# AESP_One_01.net
KiCad netlist of a schematic drawn in EAGLE
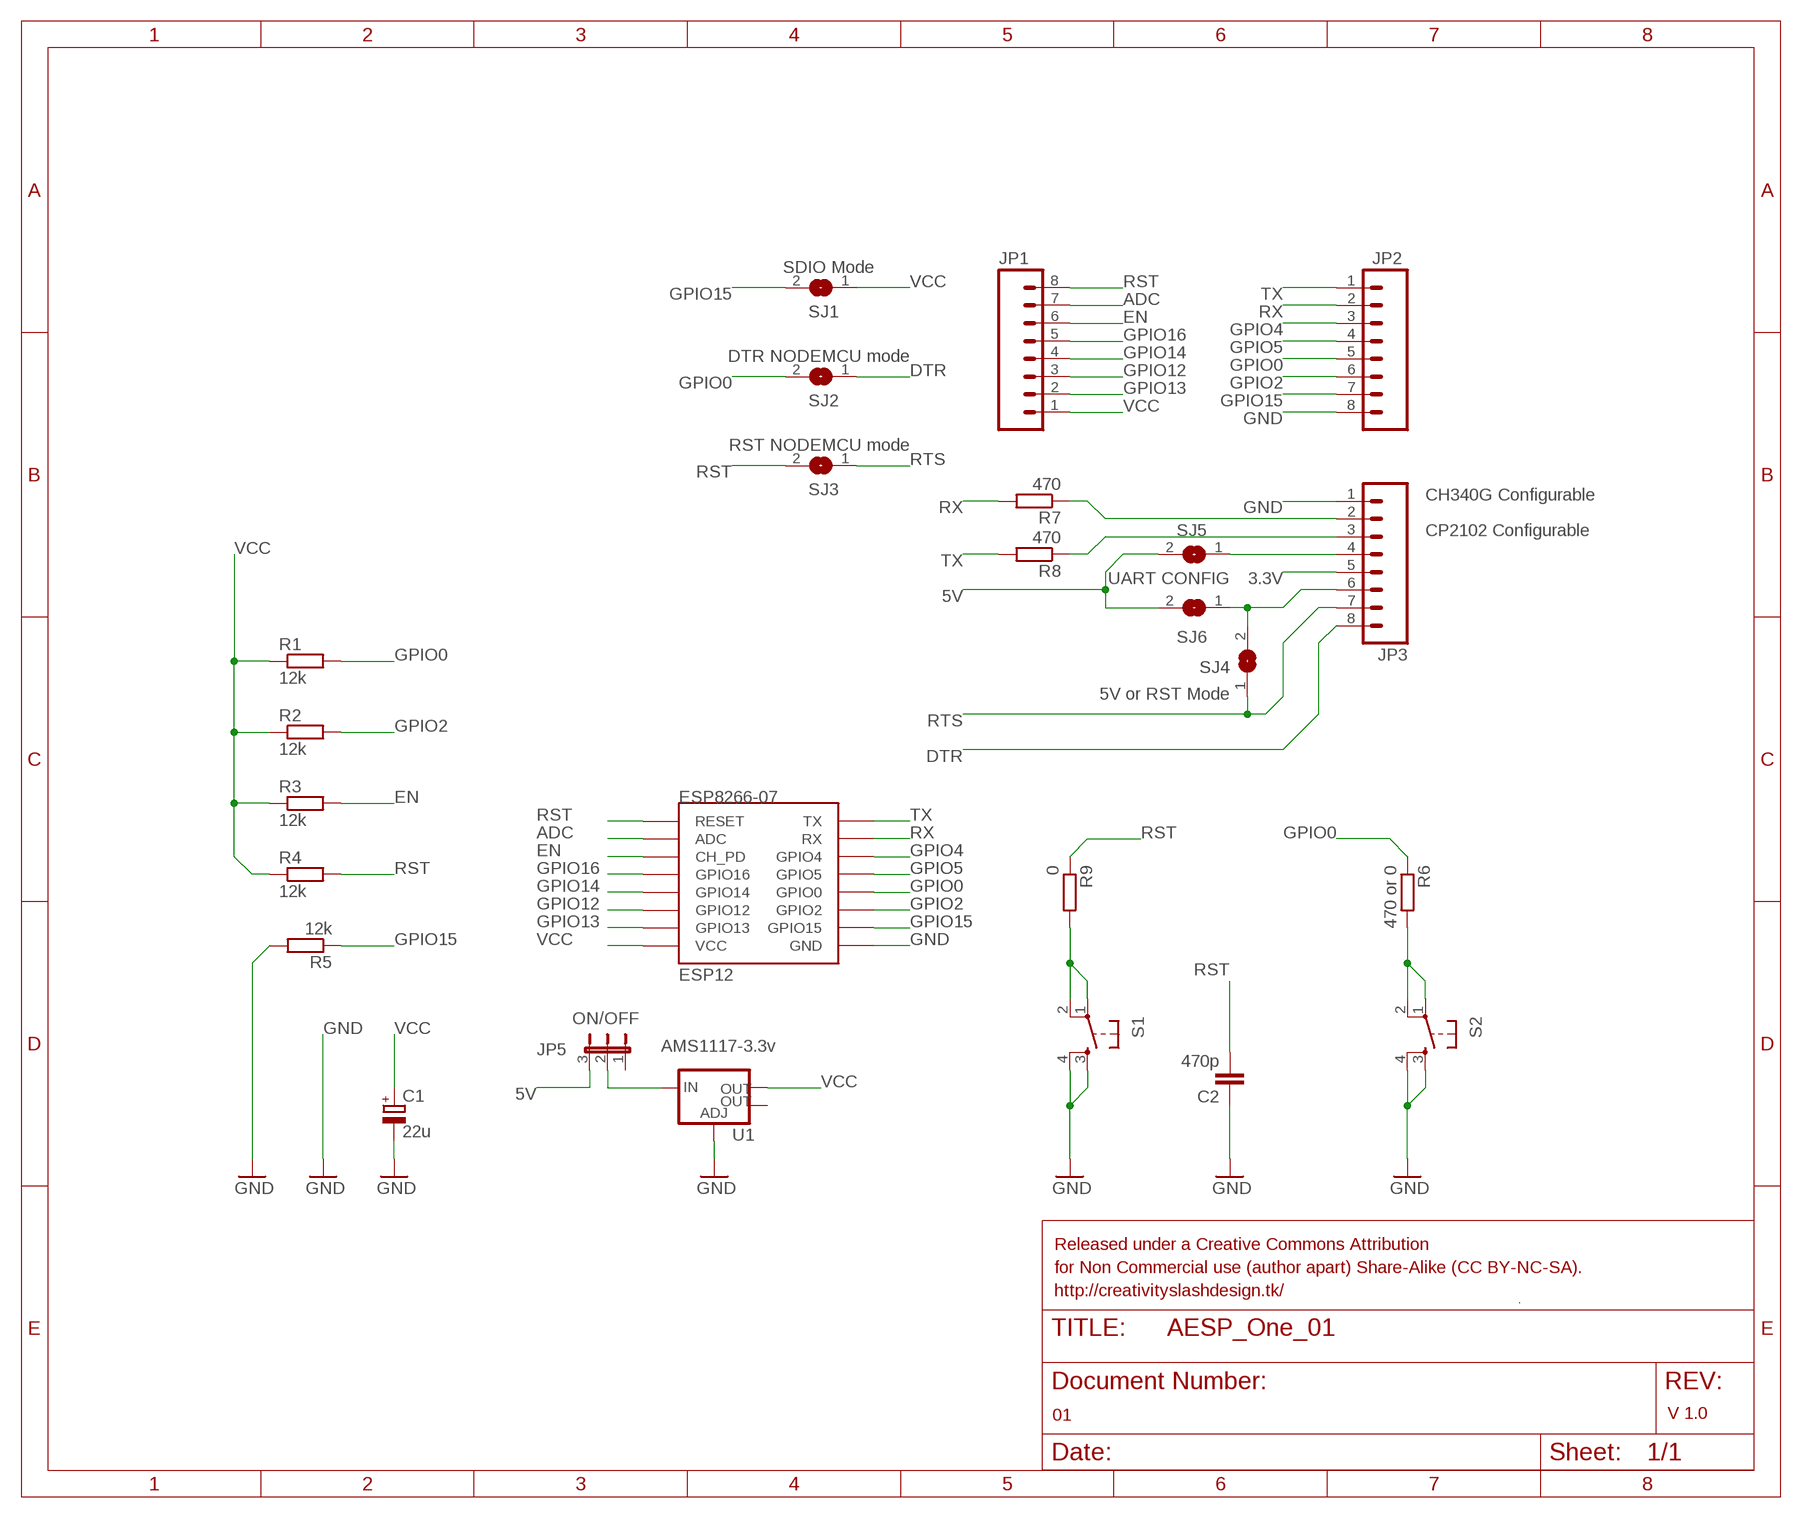
[diagram p0: schematic, sheet 1]

(export (version "E")
  (design (tool "Eeschema 10.0.6"))
  (components
    (comp (ref "C1")
      (value "22u")
      (footprint "eagle-import:140CLH-0810")
      (libsource (lib "eagle-import") (part "CPOL-EU140CLH-0810"))
    )
    (comp (ref "C2")
      (value "470p")
      (footprint "eagle-import:C0805")
      (libsource (lib "eagle-import") (part "C-EUC0805"))
    )
    (comp (ref "ESP8266-07")
      (value "ESP12")
      (footprint "eagle-import:ESP12")
      (libsource (lib "eagle-import") (part "ESP12"))
    )
    (comp (ref "JP1")
      (value "M08LONGPADS")
      (footprint "eagle-import:1X08_LONGPADS")
      (libsource (lib "eagle-import") (part "M08LONGPADS"))
    )
    (comp (ref "JP2")
      (value "M08LONGPADS")
      (footprint "eagle-import:1X08_LONGPADS")
      (libsource (lib "eagle-import") (part "M08LONGPADS"))
    )
    (comp (ref "JP3")
      (value "M08LONGPADS")
      (footprint "eagle-import:1X08_LONGPADS")
      (libsource (lib "eagle-import") (part "M08LONGPADS"))
    )
    (comp (ref "JP5")
      (value "ON/OFF")
      (footprint "eagle-import:JP2W")
      (libsource (lib "eagle-import") (part "JP2W"))
    )
    (comp (ref "R1")
      (value "12k")
      (footprint "eagle-import:M0805")
      (libsource (lib "eagle-import") (part "R-EU_M0805"))
    )
    (comp (ref "R2")
      (value "12k")
      (footprint "eagle-import:M0805")
      (libsource (lib "eagle-import") (part "R-EU_M0805"))
    )
    (comp (ref "R3")
      (value "12k")
      (footprint "eagle-import:M0805")
      (libsource (lib "eagle-import") (part "R-EU_M0805"))
    )
    (comp (ref "R4")
      (value "12k")
      (footprint "eagle-import:M0805")
      (libsource (lib "eagle-import") (part "R-EU_M0805"))
    )
    (comp (ref "R5")
      (value "12k")
      (footprint "eagle-import:M0805")
      (libsource (lib "eagle-import") (part "R-EU_M0805"))
    )
    (comp (ref "R6")
      (value "470 or 0")
      (footprint "eagle-import:M0805")
      (libsource (lib "eagle-import") (part "R-EU_M0805"))
    )
    (comp (ref "R7")
      (value "470")
      (footprint "eagle-import:M0805")
      (libsource (lib "eagle-import") (part "R-EU_M0805"))
    )
    (comp (ref "R8")
      (value "470")
      (footprint "eagle-import:M0805")
      (libsource (lib "eagle-import") (part "R-EU_M0805"))
    )
    (comp (ref "R9")
      (value "0")
      (footprint "eagle-import:M0805")
      (libsource (lib "eagle-import") (part "R-EU_M0805"))
    )
    (comp (ref "S1")
      (value "TAC_SWITCHSMD")
      (footprint "eagle-import:TACTILE-SWITCH-SMD")
      (libsource (lib "eagle-import") (part "TAC_SWITCHSMD"))
    )
    (comp (ref "S2")
      (value "TAC_SWITCHSMD")
      (footprint "eagle-import:TACTILE-SWITCH-SMD")
      (libsource (lib "eagle-import") (part "TAC_SWITCHSMD"))
    )
    (comp (ref "SJ1")
      (value "SDIO Mode")
      (footprint "eagle-import:SJ")
      (libsource (lib "eagle-import") (part "SJ"))
    )
    (comp (ref "SJ2")
      (value "DTR NODEMCU mode")
      (footprint "eagle-import:SJ")
      (libsource (lib "eagle-import") (part "SJ"))
    )
    (comp (ref "SJ3")
      (value "RST NODEMCU mode")
      (footprint "eagle-import:SJ")
      (libsource (lib "eagle-import") (part "SJ"))
    )
    (comp (ref "SJ4")
      (value "5V or RST Mode")
      (footprint "eagle-import:SJ")
      (libsource (lib "eagle-import") (part "SJ"))
    )
    (comp (ref "SJ5") (value "SJ") (footprint "eagle-import:SJ") (libsource (lib "eagle-import") (part "SJ")))
    (comp (ref "SJ6") (value "SJ") (footprint "eagle-import:SJ") (libsource (lib "eagle-import") (part "SJ")))
    (comp (ref "U1")
      (value "AMS1117-3.3v")
      (footprint "eagle-import:SOT223")
      (libsource (lib "eagle-import") (part "V_REG_LM1117SOT223"))
    )
  )
  (nets
    (net (code "1") (name "/3.3V") (class "Default")
      (node (ref "JP3") (pin "5") (pinfunction "5_5") (pintype "passive"))
    )
    (net (code "2") (name "/5V") (class "Default")
      (node (ref "JP5") (pin "3") (pinfunction "3_3") (pintype "passive"))
      (node (ref "SJ5") (pin "2") (pinfunction "2_2") (pintype "passive"))
      (node (ref "SJ6") (pin "2") (pinfunction "2_2") (pintype "passive"))
    )
    (net (code "3") (name "/ADC") (class "Default")
      (node (ref "ESP8266-07") (pin "ADC") (pinfunction "ADC_ADC") (pintype "bidirectional"))
      (node (ref "JP1") (pin "7") (pinfunction "7_7") (pintype "passive"))
    )
    (net (code "4") (name "/DTR") (class "Default")
      (node (ref "JP3") (pin "8") (pinfunction "8_8") (pintype "passive"))
      (node (ref "SJ2") (pin "1") (pinfunction "1_1") (pintype "passive"))
    )
    (net (code "5") (name "/EN") (class "Default")
      (node (ref "ESP8266-07") (pin "CH_PD") (pinfunction "CH_PD_CH_PD") (pintype "bidirectional"))
      (node (ref "JP1") (pin "6") (pinfunction "6_6") (pintype "passive"))
      (node (ref "R3") (pin "2") (pinfunction "2_2") (pintype "passive"))
    )
    (net (code "6") (name "/GPIO0") (class "Default")
      (node (ref "ESP8266-07") (pin "GPIO0") (pinfunction "GPIO0_GPIO0") (pintype "bidirectional"))
      (node (ref "JP2") (pin "5") (pinfunction "5_5") (pintype "passive"))
      (node (ref "R1") (pin "2") (pinfunction "2_2") (pintype "passive"))
      (node (ref "R6") (pin "1") (pinfunction "1_1") (pintype "passive"))
      (node (ref "SJ2") (pin "2") (pinfunction "2_2") (pintype "passive"))
    )
    (net (code "7") (name "/GPIO2") (class "Default")
      (node (ref "ESP8266-07") (pin "GPIO2") (pinfunction "GPIO2_GPIO2") (pintype "bidirectional"))
      (node (ref "JP2") (pin "6") (pinfunction "6_6") (pintype "passive"))
      (node (ref "R2") (pin "2") (pinfunction "2_2") (pintype "passive"))
    )
    (net (code "8") (name "/GPIO4") (class "Default")
      (node (ref "ESP8266-07") (pin "GPIO4") (pinfunction "GPIO4_GPIO4") (pintype "bidirectional"))
      (node (ref "JP2") (pin "3") (pinfunction "3_3") (pintype "passive"))
    )
    (net (code "9") (name "/GPIO5") (class "Default")
      (node (ref "ESP8266-07") (pin "GPIO5") (pinfunction "GPIO5_GPIO5") (pintype "bidirectional"))
      (node (ref "JP2") (pin "4") (pinfunction "4_4") (pintype "passive"))
    )
    (net (code "10") (name "/GPIO12") (class "Default")
      (node (ref "ESP8266-07") (pin "GPIO12") (pinfunction "GPIO12_GPIO12") (pintype "bidirectional"))
      (node (ref "JP1") (pin "3") (pinfunction "3_3") (pintype "passive"))
    )
    (net (code "11") (name "/GPIO13") (class "Default")
      (node (ref "ESP8266-07") (pin "GPIO13") (pinfunction "GPIO13_GPIO13") (pintype "bidirectional"))
      (node (ref "JP1") (pin "2") (pinfunction "2_2") (pintype "passive"))
    )
    (net (code "12") (name "/GPIO14") (class "Default")
      (node (ref "ESP8266-07") (pin "GPIO14") (pinfunction "GPIO14_GPIO14") (pintype "bidirectional"))
      (node (ref "JP1") (pin "4") (pinfunction "4_4") (pintype "passive"))
    )
    (net (code "13") (name "/GPIO15") (class "Default")
      (node (ref "ESP8266-07") (pin "GPIO15") (pinfunction "GPIO15_GPIO15") (pintype "bidirectional"))
      (node (ref "JP2") (pin "7") (pinfunction "7_7") (pintype "passive"))
      (node (ref "R5") (pin "1") (pinfunction "1_1") (pintype "passive"))
      (node (ref "SJ1") (pin "2") (pinfunction "2_2") (pintype "passive"))
    )
    (net (code "14") (name "/GPIO16") (class "Default")
      (node (ref "ESP8266-07") (pin "GPIO16") (pinfunction "GPIO16_GPIO16") (pintype "bidirectional"))
      (node (ref "JP1") (pin "5") (pinfunction "5_5") (pintype "passive"))
    )
    (net (code "15") (name "/RST") (class "Default")
      (node (ref "C2") (pin "2") (pinfunction "2_2") (pintype "passive"))
      (node (ref "ESP8266-07") (pin "RESET") (pinfunction "RESET_RESET") (pintype "bidirectional"))
      (node (ref "JP1") (pin "8") (pinfunction "8_8") (pintype "passive"))
      (node (ref "R4") (pin "2") (pinfunction "2_2") (pintype "passive"))
      (node (ref "R9") (pin "1") (pinfunction "1_1") (pintype "passive"))
      (node (ref "SJ3") (pin "2") (pinfunction "2_2") (pintype "passive"))
    )
    (net (code "16") (name "/RTS") (class "Default")
      (node (ref "JP3") (pin "7") (pinfunction "7_7") (pintype "passive"))
      (node (ref "SJ3") (pin "1") (pinfunction "1_1") (pintype "passive"))
      (node (ref "SJ4") (pin "1") (pinfunction "1_1") (pintype "passive"))
    )
    (net (code "17") (name "/RX") (class "Default")
      (node (ref "ESP8266-07") (pin "RX") (pinfunction "RX_RX") (pintype "bidirectional"))
      (node (ref "JP2") (pin "2") (pinfunction "2_2") (pintype "passive"))
      (node (ref "R7") (pin "2") (pinfunction "2_2") (pintype "passive"))
    )
    (net (code "18") (name "/TX") (class "Default")
      (node (ref "ESP8266-07") (pin "TX") (pinfunction "TX_TX") (pintype "bidirectional"))
      (node (ref "JP2") (pin "1") (pinfunction "1_1") (pintype "passive"))
      (node (ref "R8") (pin "2") (pinfunction "2_2") (pintype "passive"))
    )
    (net (code "19") (name "/VCC") (class "Default")
      (node (ref "C1") (pin "+") (pinfunction "+_+") (pintype "passive"))
      (node (ref "ESP8266-07") (pin "VCC") (pinfunction "VCC_VCC") (pintype "bidirectional"))
      (node (ref "JP1") (pin "1") (pinfunction "1_1") (pintype "passive"))
      (node (ref "R1") (pin "1") (pinfunction "1_1") (pintype "passive"))
      (node (ref "R2") (pin "1") (pinfunction "1_1") (pintype "passive"))
      (node (ref "R3") (pin "1") (pinfunction "1_1") (pintype "passive"))
      (node (ref "R4") (pin "1") (pinfunction "1_1") (pintype "passive"))
      (node (ref "SJ1") (pin "1") (pinfunction "1_1") (pintype "passive"))
      (node (ref "U1") (pin "2") (pinfunction "OUT_2") (pintype "output"))
    )
    (net (code "20") (name "GND") (class "Default")
      (node (ref "C1") (pin "-") (pinfunction "-_-") (pintype "passive"))
      (node (ref "C2") (pin "1") (pinfunction "1_1") (pintype "passive"))
      (node (ref "ESP8266-07") (pin "GND") (pinfunction "GND_GND") (pintype "bidirectional"))
      (node (ref "JP2") (pin "8") (pinfunction "8_8") (pintype "passive"))
      (node (ref "JP3") (pin "1") (pinfunction "1_1") (pintype "passive"))
      (node (ref "R5") (pin "2") (pinfunction "2_2") (pintype "passive"))
      (node (ref "S1") (pin "3") (pinfunction "3_3") (pintype "passive"))
      (node (ref "S1") (pin "4") (pinfunction "4_4") (pintype "passive"))
      (node (ref "S2") (pin "3") (pinfunction "3_3") (pintype "passive"))
      (node (ref "S2") (pin "4") (pinfunction "4_4") (pintype "passive"))
      (node (ref "U1") (pin "1") (pinfunction "ADJ_1") (pintype "input"))
    )
    (net (code "21") (name "Net-(JP3-Pad2)") (class "Default")
      (node (ref "JP3") (pin "2") (pinfunction "2_2") (pintype "passive"))
      (node (ref "R7") (pin "1") (pinfunction "1_1") (pintype "passive"))
    )
    (net (code "22") (name "Net-(JP3-Pad3)") (class "Default")
      (node (ref "JP3") (pin "3") (pinfunction "3_3") (pintype "passive"))
      (node (ref "R8") (pin "1") (pinfunction "1_1") (pintype "passive"))
    )
    (net (code "23") (name "Net-(JP3-Pad4)") (class "Default")
      (node (ref "JP3") (pin "4") (pinfunction "4_4") (pintype "passive"))
      (node (ref "SJ5") (pin "1") (pinfunction "1_1") (pintype "passive"))
    )
    (net (code "24") (name "Net-(JP3-Pad6)") (class "Default")
      (node (ref "JP3") (pin "6") (pinfunction "6_6") (pintype "passive"))
      (node (ref "SJ4") (pin "2") (pinfunction "2_2") (pintype "passive"))
      (node (ref "SJ6") (pin "1") (pinfunction "1_1") (pintype "passive"))
    )
    (net (code "25") (name "Net-(R6-Pad2)") (class "Default")
      (node (ref "R6") (pin "2") (pinfunction "2_2") (pintype "passive"))
      (node (ref "S2") (pin "1") (pinfunction "1_1") (pintype "passive"))
      (node (ref "S2") (pin "2") (pinfunction "2_2") (pintype "passive"))
    )
    (net (code "26") (name "Net-(R9-Pad2)") (class "Default")
      (node (ref "R9") (pin "2") (pinfunction "2_2") (pintype "passive"))
      (node (ref "S1") (pin "1") (pinfunction "1_1") (pintype "passive"))
      (node (ref "S1") (pin "2") (pinfunction "2_2") (pintype "passive"))
    )
    (net (code "27") (name "Net-(U1-IN)") (class "Default")
      (node (ref "JP5") (pin "2") (pinfunction "2_2") (pintype "passive"))
      (node (ref "U1") (pin "3") (pinfunction "IN_3") (pintype "input"))
    )
    (net (code "28") (name "unconnected-(JP5-Pad1)") (class "Default")
      (node (ref "JP5") (pin "1") (pinfunction "1_1") (pintype "passive"))
    )
    (net (code "29") (name "unconnected-(U1-OUT-Pad4)") (class "Default")
      (node (ref "U1") (pin "4") (pinfunction "OUT_4") (pintype "output"))
    )
  )
)
